# R8-o7.net
KiCad netlist of a schematic drawn in EAGLE
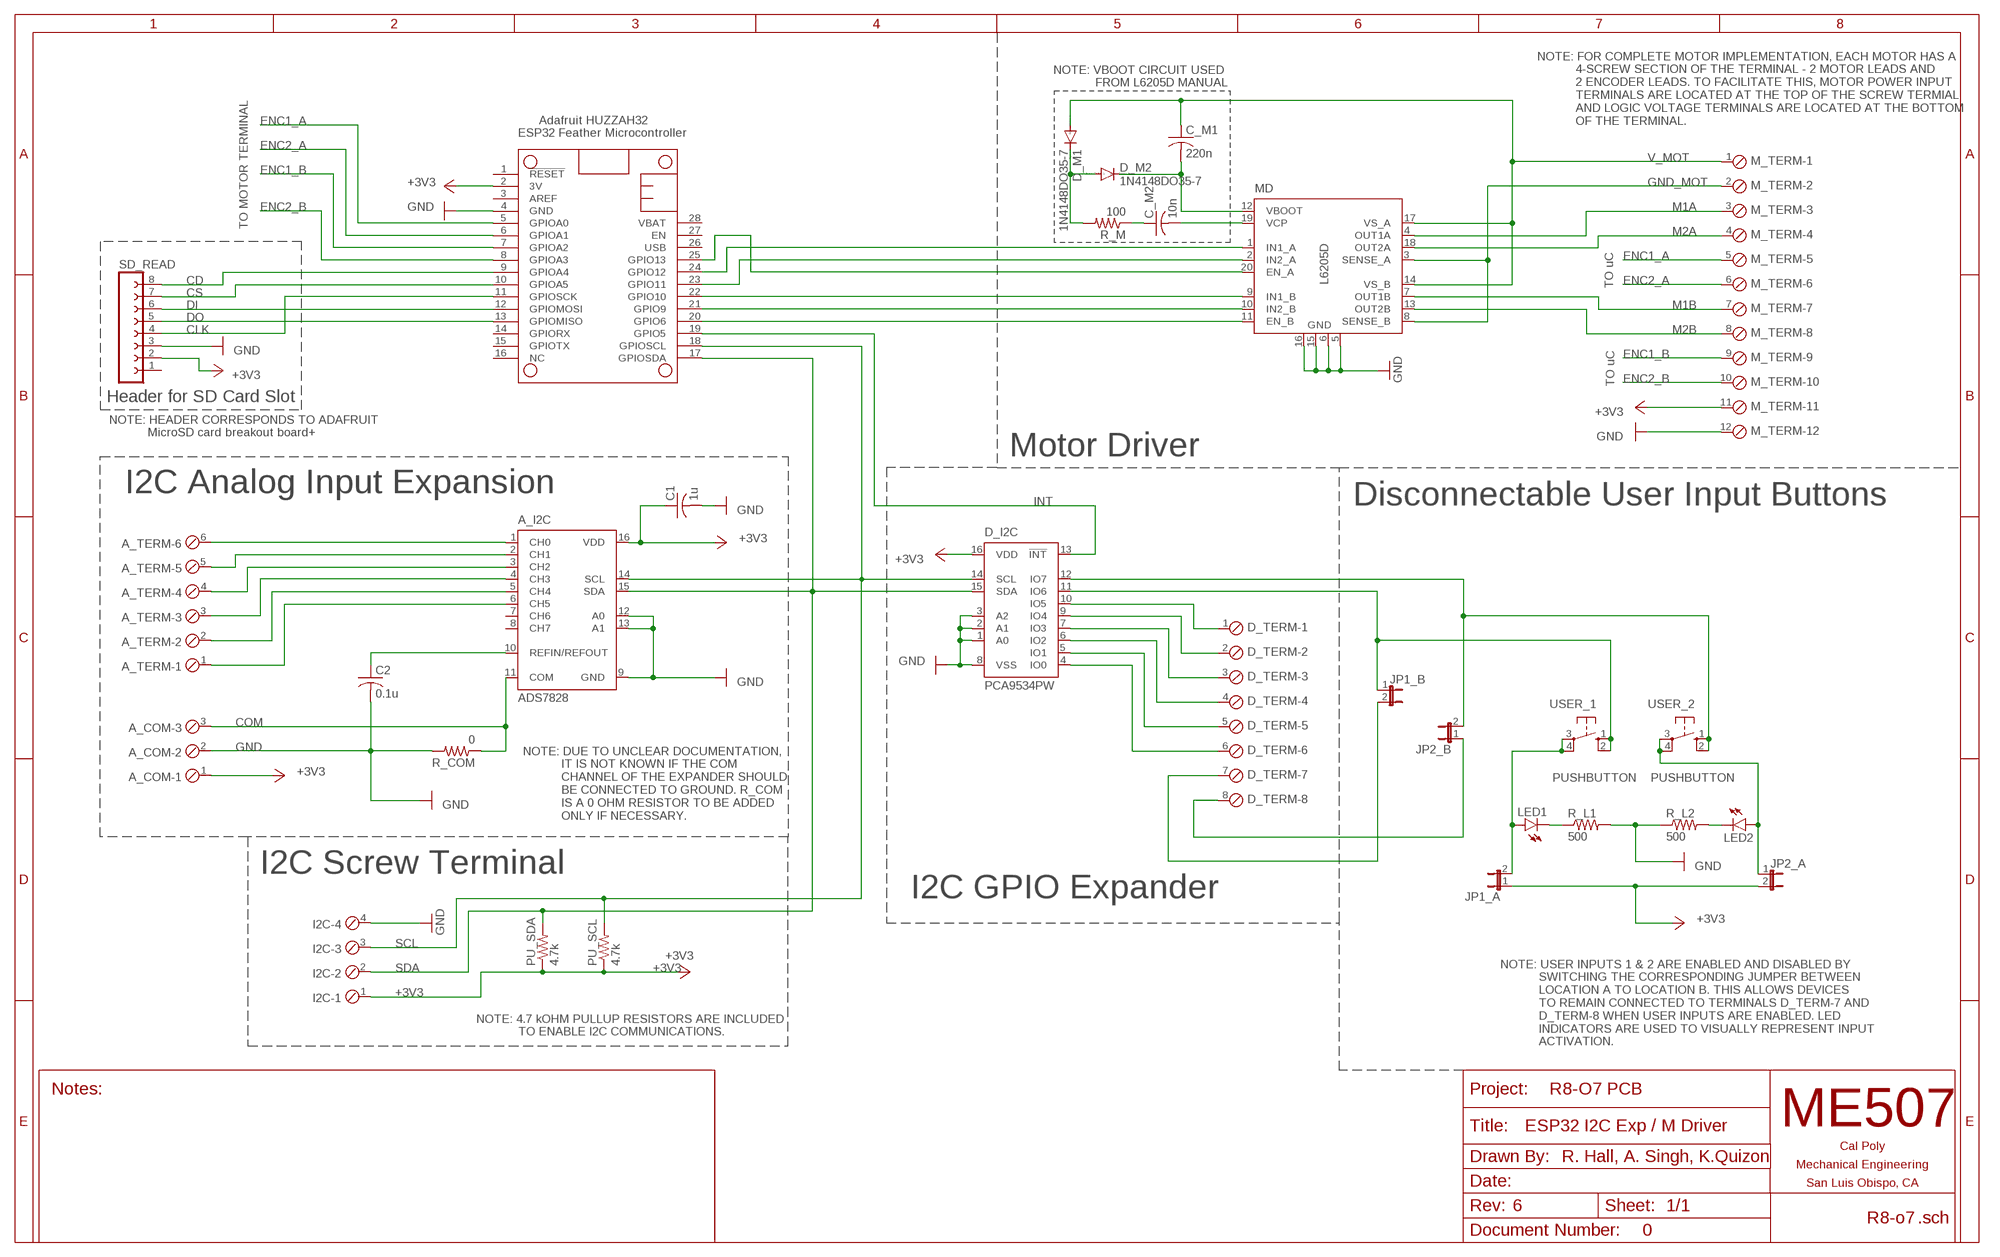
[diagram p0: schematic, sheet 1]

(export (version "E")
  (design (tool "Eeschema 10.0.6"))
  (components
    (comp (ref "A_COM")
      (value "SCREWTERM_3P_254")
      (footprint "eagle-import:3POL254")
      (libsource (lib "eagle-import") (part "SCREWTERM_3P_254"))
    )
    (comp (ref "A_I2C")
      (value "ADS7828")
      (footprint "eagle-import:TSSOP16-PW")
      (fields (field (name "MF") "TEXAS INSTRUMENTS") (field (name "MPN") "ADS7828E/250"))
      (libsource (lib "eagle-import") (part "ADS7828"))
    )
    (comp (ref "A_TERM")
      (value "SCREWTERM_6P_254")
      (footprint "eagle-import:6POL254")
      (libsource (lib "eagle-import") (part "SCREWTERM_6P_254"))
    )
    (comp (ref "C1")
      (value "1u")
      (footprint "eagle-import:C0805")
      (libsource (lib "eagle-import") (part "C-USC0805"))
    )
    (comp (ref "C2")
      (value "0.1u")
      (footprint "eagle-import:C0805")
      (libsource (lib "eagle-import") (part "C-USC0805"))
    )
    (comp (ref "C_M1")
      (value "220n")
      (footprint "eagle-import:C0805")
      (libsource (lib "eagle-import") (part "C-USC0805"))
    )
    (comp (ref "C_M2")
      (value "10n")
      (footprint "eagle-import:C0805")
      (libsource (lib "eagle-import") (part "C-USC0805"))
    )
    (comp (ref "D_I2C")
      (value "PCA9534PW")
      (footprint "eagle-import:TSSOP16")
      (libsource (lib "eagle-import") (part "PCA9534PW"))
    )
    (comp (ref "D_M1")
      (value "1N4148DO35-7")
      (footprint "eagle-import:DO35-7")
      (libsource (lib "eagle-import") (part "1N4148DO35-7"))
    )
    (comp (ref "D_M2")
      (value "1N4148DO35-7")
      (footprint "eagle-import:DO35-7")
      (libsource (lib "eagle-import") (part "1N4148DO35-7"))
    )
    (comp (ref "D_TERM")
      (value "SCREWTERM_8P_254")
      (footprint "eagle-import:8POL254")
      (libsource (lib "eagle-import") (part "SCREWTERM_8P_254"))
    )
    (comp (ref "FTHRWNG")
      (value "FEATHERWINGEXTENDED_BOTH_ENDS")
      (footprint "eagle-import:FEATHERWING")
      (libsource (lib "eagle-import") (part "FEATHERWINGEXTENDED_BOTH_ENDS"))
    )
    (comp (ref "I2C")
      (value "SCREWTERM_4P_254")
      (footprint "eagle-import:4POL254")
      (libsource (lib "eagle-import") (part "SCREWTERM_4P_254"))
    )
    (comp (ref "JP1_A")
      (value "JP1E")
      (footprint "eagle-import:JP1")
      (libsource (lib "eagle-import") (part "JP1E"))
    )
    (comp (ref "JP1_B")
      (value "JP1E")
      (footprint "eagle-import:JP1")
      (libsource (lib "eagle-import") (part "JP1E"))
    )
    (comp (ref "JP2_A")
      (value "JP1E")
      (footprint "eagle-import:JP1")
      (libsource (lib "eagle-import") (part "JP1E"))
    )
    (comp (ref "JP2_B")
      (value "JP1E")
      (footprint "eagle-import:JP1")
      (libsource (lib "eagle-import") (part "JP1E"))
    )
    (comp (ref "LED1")
      (value "LEDCHIP-LED0805")
      (footprint "eagle-import:CHIP-LED0805")
      (libsource (lib "eagle-import") (part "LEDCHIP-LED0805"))
    )
    (comp (ref "LED2")
      (value "LEDCHIP-LED0805")
      (footprint "eagle-import:CHIP-LED0805")
      (libsource (lib "eagle-import") (part "LEDCHIP-LED0805"))
    )
    (comp (ref "MD")
      (value "L6205D")
      (footprint "eagle-import:SO20")
      (libsource (lib "eagle-import") (part "L6205D"))
    )
    (comp (ref "M_TERM")
      (value "SCREWTERM_12P_254")
      (footprint "eagle-import:12POL254")
      (libsource (lib "eagle-import") (part "SCREWTERM_12P_254"))
    )
    (comp (ref "PU_SCL")
      (value "4.7k")
      (footprint "eagle-import:M0805")
      (libsource (lib "eagle-import") (part "R-US_M0805"))
    )
    (comp (ref "PU_SDA")
      (value "4.7k")
      (footprint "eagle-import:M0805")
      (libsource (lib "eagle-import") (part "R-US_M0805"))
    )
    (comp (ref "R_COM")
      (value "0")
      (footprint "eagle-import:M0805")
      (libsource (lib "eagle-import") (part "R-US_M0805"))
    )
    (comp (ref "R_L1")
      (value "500")
      (footprint "eagle-import:M0805")
      (libsource (lib "eagle-import") (part "R-US_M0805"))
    )
    (comp (ref "R_L2")
      (value "500")
      (footprint "eagle-import:M0805")
      (libsource (lib "eagle-import") (part "R-US_M0805"))
    )
    (comp (ref "R_M")
      (value "100")
      (footprint "eagle-import:M0805")
      (libsource (lib "eagle-import") (part "R-US_M0805"))
    )
    (comp (ref "SD_READ")
      (value "FE08-1")
      (footprint "eagle-import:FE08")
      (libsource (lib "eagle-import") (part "FE08-1"))
    )
    (comp (ref "USER_1")
      (value "PUSHBUTTON")
      (footprint "eagle-import:B3F-10XX")
      (fields (field (name "MPN") "B3F-1000"))
      (libsource (lib "eagle-import") (part "PUSHBUTTON"))
    )
    (comp (ref "USER_2")
      (value "PUSHBUTTON")
      (footprint "eagle-import:B3F-10XX")
      (fields (field (name "MPN") "B3F-1000"))
      (libsource (lib "eagle-import") (part "PUSHBUTTON"))
    )
  )
  (nets
    (net (code "1") (name "+3V3") (class "Default")
      (node (ref "A_COM") (pin "1") (pinfunction "1_1") (pintype "passive"))
      (node (ref "A_I2C") (pin "16") (pinfunction "VDD_16") (pintype "power_in"))
      (node (ref "C1") (pin "1") (pinfunction "1_1") (pintype "passive"))
      (node (ref "D_I2C") (pin "16") (pinfunction "VDD_16") (pintype "power_in"))
      (node (ref "FTHRWNG") (pin "2") (pinfunction "3V_2") (pintype "power_in"))
      (node (ref "I2C") (pin "1") (pinfunction "1_1") (pintype "passive"))
      (node (ref "JP1_A") (pin "1") (pinfunction "1_1") (pintype "passive"))
      (node (ref "JP2_A") (pin "2") (pinfunction "2_2") (pintype "passive"))
      (node (ref "M_TERM") (pin "11") (pinfunction "1_11") (pintype "passive"))
      (node (ref "PU_SCL") (pin "1") (pinfunction "1_1") (pintype "passive"))
      (node (ref "PU_SDA") (pin "1") (pinfunction "1_1") (pintype "passive"))
      (node (ref "SD_READ") (pin "2") (pinfunction "2_2") (pintype "passive"))
    )
    (net (code "2") (name "/CD") (class "Default")
      (node (ref "FTHRWNG") (pin "9") (pinfunction "GPIOA4_9") (pintype "bidirectional"))
      (node (ref "SD_READ") (pin "8") (pinfunction "8_8") (pintype "passive"))
    )
    (net (code "3") (name "/CLK") (class "Default")
      (node (ref "FTHRWNG") (pin "11") (pinfunction "GPIOSCK_11") (pintype "bidirectional"))
      (node (ref "SD_READ") (pin "4") (pinfunction "4_4") (pintype "passive"))
    )
    (net (code "4") (name "/COM") (class "Default")
      (node (ref "A_COM") (pin "3") (pinfunction "1_3") (pintype "passive"))
      (node (ref "A_I2C") (pin "11") (pinfunction "COM_11") (pintype "input"))
      (node (ref "R_COM") (pin "1") (pinfunction "1_1") (pintype "passive"))
    )
    (net (code "5") (name "/CS") (class "Default")
      (node (ref "FTHRWNG") (pin "10") (pinfunction "GPIOA5_10") (pintype "bidirectional"))
      (node (ref "SD_READ") (pin "7") (pinfunction "7_7") (pintype "passive"))
    )
    (net (code "6") (name "/DI") (class "Default")
      (node (ref "FTHRWNG") (pin "12") (pinfunction "GPIOMOSI_12") (pintype "bidirectional"))
      (node (ref "SD_READ") (pin "6") (pinfunction "6_6") (pintype "passive"))
    )
    (net (code "7") (name "/DO") (class "Default")
      (node (ref "FTHRWNG") (pin "13") (pinfunction "GPIOMISO_13") (pintype "bidirectional"))
      (node (ref "SD_READ") (pin "5") (pinfunction "5_5") (pintype "passive"))
    )
    (net (code "8") (name "/ENC1_A") (class "Default")
      (node (ref "FTHRWNG") (pin "5") (pinfunction "GPIOA0_5") (pintype "bidirectional"))
      (node (ref "M_TERM") (pin "5") (pinfunction "1_5") (pintype "passive"))
    )
    (net (code "9") (name "/ENC1_B") (class "Default")
      (node (ref "FTHRWNG") (pin "7") (pinfunction "GPIOA2_7") (pintype "bidirectional"))
      (node (ref "M_TERM") (pin "9") (pinfunction "1_9") (pintype "passive"))
    )
    (net (code "10") (name "/ENC2_A") (class "Default")
      (node (ref "FTHRWNG") (pin "6") (pinfunction "GPIOA1_6") (pintype "bidirectional"))
      (node (ref "M_TERM") (pin "6") (pinfunction "1_6") (pintype "passive"))
    )
    (net (code "11") (name "/ENC2_B") (class "Default")
      (node (ref "FTHRWNG") (pin "8") (pinfunction "GPIOA3_8") (pintype "bidirectional"))
      (node (ref "M_TERM") (pin "10") (pinfunction "1_10") (pintype "passive"))
    )
    (net (code "12") (name "/GND_MOT") (class "Default")
      (node (ref "MD") (pin "3") (pinfunction "SENSE_A_3") (pintype "input"))
      (node (ref "MD") (pin "8") (pinfunction "SENSE_B_8") (pintype "input"))
      (node (ref "M_TERM") (pin "2") (pinfunction "1_2") (pintype "passive"))
    )
    (net (code "13") (name "/INT") (class "Default")
      (node (ref "D_I2C") (pin "13") (pinfunction "~{INT}_13") (pintype "open_collector"))
      (node (ref "FTHRWNG") (pin "19") (pinfunction "GPIO5_19") (pintype "bidirectional"))
    )
    (net (code "14") (name "/M1A") (class "Default")
      (node (ref "MD") (pin "4") (pinfunction "OUT1A_4") (pintype "output"))
      (node (ref "M_TERM") (pin "3") (pinfunction "1_3") (pintype "passive"))
    )
    (net (code "15") (name "/M1B") (class "Default")
      (node (ref "MD") (pin "7") (pinfunction "OUT1B_7") (pintype "output"))
      (node (ref "M_TERM") (pin "7") (pinfunction "1_7") (pintype "passive"))
    )
    (net (code "16") (name "/M2A") (class "Default")
      (node (ref "MD") (pin "18") (pinfunction "OUT2A_18") (pintype "output"))
      (node (ref "M_TERM") (pin "4") (pinfunction "1_4") (pintype "passive"))
    )
    (net (code "17") (name "/M2B") (class "Default")
      (node (ref "MD") (pin "13") (pinfunction "OUT2B_13") (pintype "output"))
      (node (ref "M_TERM") (pin "8") (pinfunction "1_8") (pintype "passive"))
    )
    (net (code "18") (name "/SCL") (class "Default")
      (node (ref "A_I2C") (pin "14") (pinfunction "SCL_14") (pintype "input"))
      (node (ref "D_I2C") (pin "14") (pinfunction "SCL_14") (pintype "input"))
      (node (ref "FTHRWNG") (pin "18") (pinfunction "GPIOSCL_18") (pintype "bidirectional"))
      (node (ref "I2C") (pin "3") (pinfunction "1_3") (pintype "passive"))
      (node (ref "PU_SCL") (pin "2") (pinfunction "2_2") (pintype "passive"))
    )
    (net (code "19") (name "/SDA") (class "Default")
      (node (ref "A_I2C") (pin "15") (pinfunction "SDA_15") (pintype "bidirectional"))
      (node (ref "D_I2C") (pin "15") (pinfunction "SDA_15") (pintype "bidirectional"))
      (node (ref "FTHRWNG") (pin "17") (pinfunction "GPIOSDA_17") (pintype "bidirectional"))
      (node (ref "I2C") (pin "2") (pinfunction "1_2") (pintype "passive"))
      (node (ref "PU_SDA") (pin "2") (pinfunction "2_2") (pintype "passive"))
    )
    (net (code "20") (name "/USB") (class "Default")
      (node (ref "FTHRWNG") (pin "26") (pinfunction "USB_26") (pintype "power_in"))
    )
    (net (code "21") (name "/VBAT") (class "Default")
      (node (ref "FTHRWNG") (pin "28") (pinfunction "VBAT_28") (pintype "power_in"))
    )
    (net (code "22") (name "/V_MOT") (class "Default")
      (node (ref "C_M1") (pin "1") (pinfunction "1_1") (pintype "passive"))
      (node (ref "D_M1") (pin "A") (pinfunction "A_A") (pintype "passive"))
      (node (ref "MD") (pin "14") (pinfunction "VS_B_14") (pintype "power_in"))
      (node (ref "MD") (pin "17") (pinfunction "VS_A_17") (pintype "power_in"))
      (node (ref "M_TERM") (pin "1") (pinfunction "1_1") (pintype "passive"))
    )
    (net (code "23") (name "GND") (class "Default")
      (node (ref "A_COM") (pin "2") (pinfunction "1_2") (pintype "passive"))
      (node (ref "A_I2C") (pin "12") (pinfunction "A0_12") (pintype "input"))
      (node (ref "A_I2C") (pin "13") (pinfunction "A1_13") (pintype "input"))
      (node (ref "A_I2C") (pin "9") (pinfunction "GND_9") (pintype "power_in"))
      (node (ref "C1") (pin "2") (pinfunction "2_2") (pintype "passive"))
      (node (ref "C2") (pin "2") (pinfunction "2_2") (pintype "passive"))
      (node (ref "D_I2C") (pin "1") (pinfunction "A0_1") (pintype "input"))
      (node (ref "D_I2C") (pin "2") (pinfunction "A1_2") (pintype "input"))
      (node (ref "D_I2C") (pin "3") (pinfunction "A2_3") (pintype "input"))
      (node (ref "D_I2C") (pin "8") (pinfunction "VSS_8") (pintype "power_in"))
      (node (ref "FTHRWNG") (pin "4") (pinfunction "GND_4") (pintype "power_in"))
      (node (ref "I2C") (pin "4") (pinfunction "1_4") (pintype "passive"))
      (node (ref "MD") (pin "15") (pinfunction "GND_15") (pintype "power_in"))
      (node (ref "MD") (pin "16") (pinfunction "GND_16") (pintype "power_in"))
      (node (ref "MD") (pin "5") (pinfunction "GND_5") (pintype "power_in"))
      (node (ref "MD") (pin "6") (pinfunction "GND_6") (pintype "power_in"))
      (node (ref "M_TERM") (pin "12") (pinfunction "1_12") (pintype "passive"))
      (node (ref "R_COM") (pin "2") (pinfunction "2_2") (pintype "passive"))
      (node (ref "R_L1") (pin "2") (pinfunction "2_2") (pintype "passive"))
      (node (ref "R_L2") (pin "1") (pinfunction "1_1") (pintype "passive"))
      (node (ref "SD_READ") (pin "3") (pinfunction "3_3") (pintype "passive"))
    )
    (net (code "24") (name "Net-(A_I2C-CH0)") (class "Default")
      (node (ref "A_I2C") (pin "1") (pinfunction "CH0_1") (pintype "input"))
      (node (ref "A_TERM") (pin "6") (pinfunction "1_6") (pintype "passive"))
    )
    (net (code "25") (name "Net-(A_I2C-CH1)") (class "Default")
      (node (ref "A_I2C") (pin "2") (pinfunction "CH1_2") (pintype "input"))
      (node (ref "A_TERM") (pin "5") (pinfunction "1_5") (pintype "passive"))
    )
    (net (code "26") (name "Net-(A_I2C-CH2)") (class "Default")
      (node (ref "A_I2C") (pin "3") (pinfunction "CH2_3") (pintype "input"))
      (node (ref "A_TERM") (pin "4") (pinfunction "1_4") (pintype "passive"))
    )
    (net (code "27") (name "Net-(A_I2C-CH3)") (class "Default")
      (node (ref "A_I2C") (pin "4") (pinfunction "CH3_4") (pintype "input"))
      (node (ref "A_TERM") (pin "3") (pinfunction "1_3") (pintype "passive"))
    )
    (net (code "28") (name "Net-(A_I2C-CH4)") (class "Default")
      (node (ref "A_I2C") (pin "5") (pinfunction "CH4_5") (pintype "input"))
      (node (ref "A_TERM") (pin "2") (pinfunction "1_2") (pintype "passive"))
    )
    (net (code "29") (name "Net-(A_I2C-CH5)") (class "Default")
      (node (ref "A_I2C") (pin "6") (pinfunction "CH5_6") (pintype "input"))
      (node (ref "A_TERM") (pin "1") (pinfunction "1_1") (pintype "passive"))
    )
    (net (code "30") (name "Net-(A_I2C-REFIN{slash}REFOUT)") (class "Default")
      (node (ref "A_I2C") (pin "10") (pinfunction "REFIN/REFOUT_10") (pintype "passive"))
      (node (ref "C2") (pin "1") (pinfunction "1_1") (pintype "passive"))
    )
    (net (code "31") (name "Net-(C_M2-Pad1)") (class "Default")
      (node (ref "C_M2") (pin "1") (pinfunction "1_1") (pintype "passive"))
      (node (ref "R_M") (pin "1") (pinfunction "1_1") (pintype "passive"))
    )
    (net (code "32") (name "Net-(D_I2C-IO0)") (class "Default")
      (node (ref "D_I2C") (pin "4") (pinfunction "IO0_4") (pintype "bidirectional"))
      (node (ref "D_TERM") (pin "6") (pinfunction "1_6") (pintype "passive"))
    )
    (net (code "33") (name "Net-(D_I2C-IO1)") (class "Default")
      (node (ref "D_I2C") (pin "5") (pinfunction "IO1_5") (pintype "bidirectional"))
      (node (ref "D_TERM") (pin "5") (pinfunction "1_5") (pintype "passive"))
    )
    (net (code "34") (name "Net-(D_I2C-IO2)") (class "Default")
      (node (ref "D_I2C") (pin "6") (pinfunction "IO2_6") (pintype "bidirectional"))
      (node (ref "D_TERM") (pin "4") (pinfunction "1_4") (pintype "passive"))
    )
    (net (code "35") (name "Net-(D_I2C-IO3)") (class "Default")
      (node (ref "D_I2C") (pin "7") (pinfunction "IO3_7") (pintype "bidirectional"))
      (node (ref "D_TERM") (pin "3") (pinfunction "1_3") (pintype "passive"))
    )
    (net (code "36") (name "Net-(D_I2C-IO4)") (class "Default")
      (node (ref "D_I2C") (pin "9") (pinfunction "IO4_9") (pintype "bidirectional"))
      (node (ref "D_TERM") (pin "2") (pinfunction "1_2") (pintype "passive"))
    )
    (net (code "37") (name "Net-(D_I2C-IO5)") (class "Default")
      (node (ref "D_I2C") (pin "10") (pinfunction "IO5_10") (pintype "bidirectional"))
      (node (ref "D_TERM") (pin "1") (pinfunction "1_1") (pintype "passive"))
    )
    (net (code "38") (name "Net-(D_I2C-IO6)") (class "Default")
      (node (ref "D_I2C") (pin "11") (pinfunction "IO6_11") (pintype "bidirectional"))
      (node (ref "JP1_B") (pin "1") (pinfunction "1_1") (pintype "passive"))
      (node (ref "USER_1") (pin "1") (pinfunction "S_1") (pintype "passive"))
      (node (ref "USER_1") (pin "2") (pinfunction "S1_2") (pintype "passive"))
    )
    (net (code "39") (name "Net-(D_I2C-IO7)") (class "Default")
      (node (ref "D_I2C") (pin "12") (pinfunction "IO7_12") (pintype "bidirectional"))
      (node (ref "JP2_B") (pin "2") (pinfunction "2_2") (pintype "passive"))
      (node (ref "USER_2") (pin "1") (pinfunction "S_1") (pintype "passive"))
      (node (ref "USER_2") (pin "2") (pinfunction "S1_2") (pintype "passive"))
    )
    (net (code "40") (name "Net-(D_M1-PadC)") (class "Default")
      (node (ref "D_M1") (pin "C") (pinfunction "C_C") (pintype "passive"))
      (node (ref "D_M2") (pin "A") (pinfunction "A_A") (pintype "passive"))
      (node (ref "R_M") (pin "2") (pinfunction "2_2") (pintype "passive"))
    )
    (net (code "41") (name "Net-(D_TERMG-1)") (class "Default")
      (node (ref "D_TERM") (pin "7") (pinfunction "1_7") (pintype "passive"))
      (node (ref "JP1_B") (pin "2") (pinfunction "2_2") (pintype "passive"))
    )
    (net (code "42") (name "Net-(D_TERMH-1)") (class "Default")
      (node (ref "D_TERM") (pin "8") (pinfunction "1_8") (pintype "passive"))
      (node (ref "JP2_B") (pin "1") (pinfunction "1_1") (pintype "passive"))
    )
    (net (code "43") (name "Net-(FTHRWNG-GPIO6)") (class "Default")
      (node (ref "FTHRWNG") (pin "20") (pinfunction "GPIO6_20") (pintype "bidirectional"))
      (node (ref "MD") (pin "11") (pinfunction "EN_B_11") (pintype "input"))
    )
    (net (code "44") (name "Net-(FTHRWNG-GPIO9)") (class "Default")
      (node (ref "FTHRWNG") (pin "21") (pinfunction "GPIO9_21") (pintype "bidirectional"))
      (node (ref "MD") (pin "10") (pinfunction "IN2_B_10") (pintype "input"))
    )
    (net (code "45") (name "Net-(FTHRWNG-GPIO10)") (class "Default")
      (node (ref "FTHRWNG") (pin "22") (pinfunction "GPIO10_22") (pintype "bidirectional"))
      (node (ref "MD") (pin "9") (pinfunction "IN1_B_9") (pintype "input"))
    )
    (net (code "46") (name "Net-(FTHRWNG-GPIO11)") (class "Default")
      (node (ref "FTHRWNG") (pin "23") (pinfunction "GPIO11_23") (pintype "bidirectional"))
      (node (ref "MD") (pin "2") (pinfunction "IN2_A_2") (pintype "input"))
    )
    (net (code "47") (name "Net-(FTHRWNG-GPIO12)") (class "Default")
      (node (ref "FTHRWNG") (pin "24") (pinfunction "GPIO12_24") (pintype "bidirectional"))
      (node (ref "MD") (pin "1") (pinfunction "IN1_A_1") (pintype "input"))
    )
    (net (code "48") (name "Net-(FTHRWNG-GPIO13)") (class "Default")
      (node (ref "FTHRWNG") (pin "25") (pinfunction "GPIO13_25") (pintype "bidirectional"))
      (node (ref "MD") (pin "20") (pinfunction "EN_A_20") (pintype "input"))
    )
    (net (code "49") (name "Net-(LED1-PadC)") (class "Default")
      (node (ref "LED1") (pin "C") (pinfunction "C_C") (pintype "passive"))
      (node (ref "R_L1") (pin "1") (pinfunction "1_1") (pintype "passive"))
    )
    (net (code "50") (name "Net-(LED2-PadC)") (class "Default")
      (node (ref "LED2") (pin "C") (pinfunction "C_C") (pintype "passive"))
      (node (ref "R_L2") (pin "2") (pinfunction "2_2") (pintype "passive"))
    )
    (net (code "51") (name "Net-(MD-VBOOT)") (class "Default")
      (node (ref "C_M1") (pin "2") (pinfunction "2_2") (pintype "passive"))
      (node (ref "D_M2") (pin "C") (pinfunction "C_C") (pintype "passive"))
      (node (ref "MD") (pin "12") (pinfunction "VBOOT_12") (pintype "power_in"))
    )
    (net (code "52") (name "Net-(MD-VCP)") (class "Default")
      (node (ref "C_M2") (pin "2") (pinfunction "2_2") (pintype "passive"))
      (node (ref "MD") (pin "19") (pinfunction "VCP_19") (pintype "power_in"))
    )
    (net (code "53") (name "Net-(USER_1-P)") (class "Default")
      (node (ref "JP1_A") (pin "2") (pinfunction "2_2") (pintype "passive"))
      (node (ref "LED1") (pin "A") (pinfunction "A_A") (pintype "passive"))
      (node (ref "USER_1") (pin "3") (pinfunction "P_3") (pintype "passive"))
      (node (ref "USER_1") (pin "4") (pinfunction "P1_4") (pintype "passive"))
    )
    (net (code "54") (name "Net-(USER_2-P)") (class "Default")
      (node (ref "JP2_A") (pin "1") (pinfunction "1_1") (pintype "passive"))
      (node (ref "LED2") (pin "A") (pinfunction "A_A") (pintype "passive"))
      (node (ref "USER_2") (pin "3") (pinfunction "P_3") (pintype "passive"))
      (node (ref "USER_2") (pin "4") (pinfunction "P1_4") (pintype "passive"))
    )
    (net (code "55") (name "unconnected-(A_I2C-CH6-Pad7)") (class "Default")
      (node (ref "A_I2C") (pin "7") (pinfunction "CH6_7") (pintype "input"))
    )
    (net (code "56") (name "unconnected-(A_I2C-CH7-Pad8)") (class "Default")
      (node (ref "A_I2C") (pin "8") (pinfunction "CH7_8") (pintype "input"))
    )
    (net (code "57") (name "unconnected-(FTHRWNG-AREF-Pad3)") (class "Default")
      (node (ref "FTHRWNG") (pin "3") (pinfunction "AREF_3") (pintype "passive"))
    )
    (net (code "58") (name "unconnected-(FTHRWNG-EN-Pad27)") (class "Default")
      (node (ref "FTHRWNG") (pin "27") (pinfunction "EN_27") (pintype "passive"))
    )
    (net (code "59") (name "unconnected-(FTHRWNG-GPIORX-Pad14)") (class "Default")
      (node (ref "FTHRWNG") (pin "14") (pinfunction "GPIORX_14") (pintype "bidirectional"))
    )
    (net (code "60") (name "unconnected-(FTHRWNG-GPIOTX-Pad15)") (class "Default")
      (node (ref "FTHRWNG") (pin "15") (pinfunction "GPIOTX_15") (pintype "bidirectional"))
    )
    (net (code "61") (name "unconnected-(FTHRWNG-NC-Pad16)") (class "Default")
      (node (ref "FTHRWNG") (pin "16") (pinfunction "NC_16") (pintype "passive"))
    )
    (net (code "62") (name "unconnected-(FTHRWNG-~{RESET}-Pad1)") (class "Default")
      (node (ref "FTHRWNG") (pin "1") (pinfunction "~{RESET}_1") (pintype "input"))
    )
    (net (code "63") (name "unconnected-(SD_READ-Pad1)") (class "Default")
      (node (ref "SD_READ") (pin "1") (pinfunction "1_1") (pintype "passive"))
    )
  )
)
